# SEX.net
KiCad netlist of a schematic drawn in Altium Designer
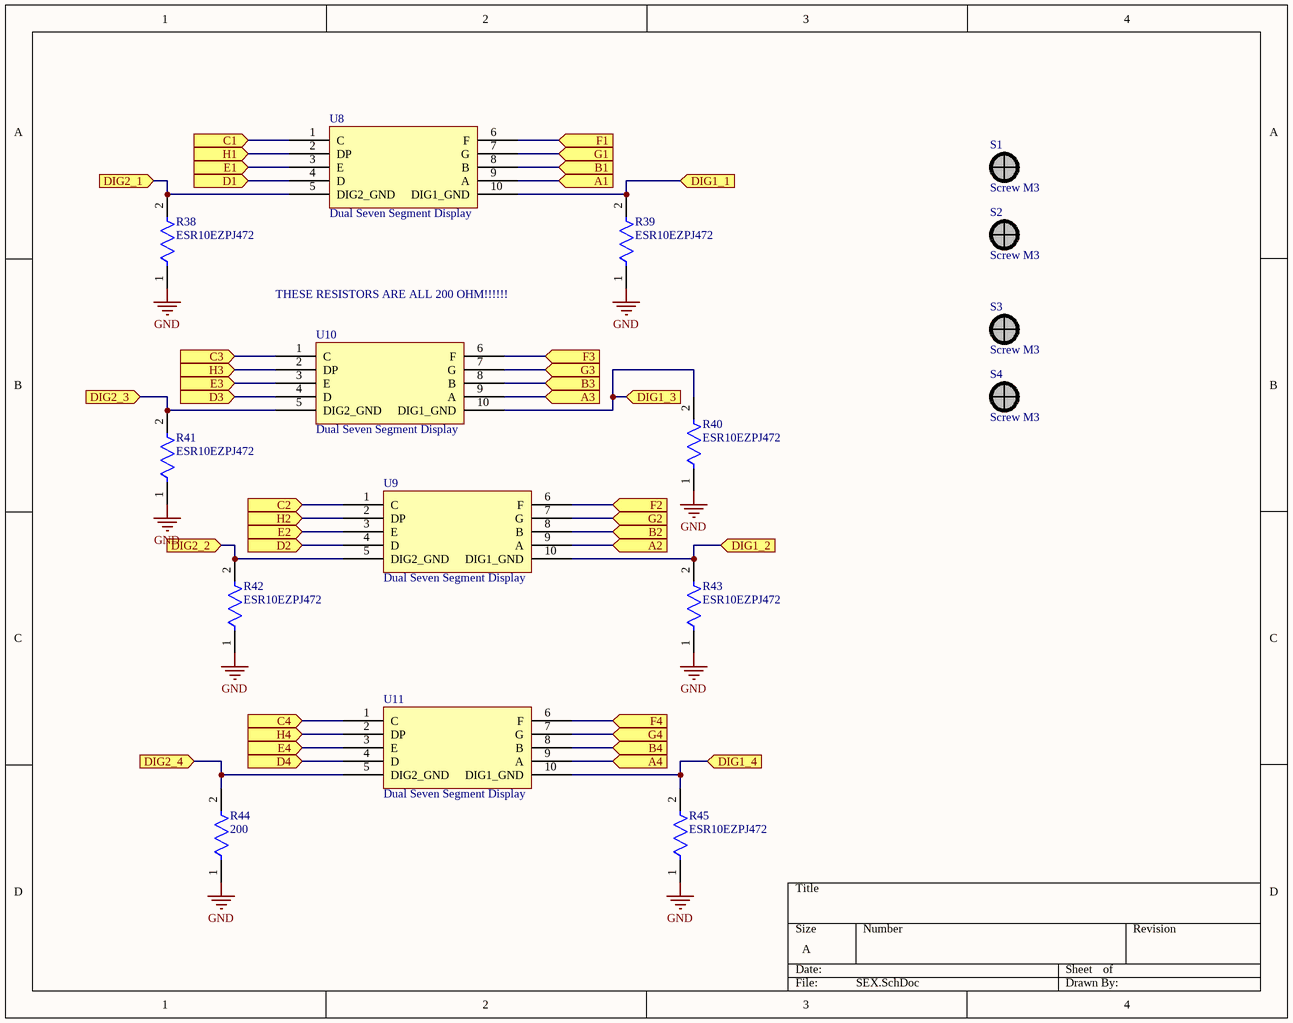
[diagram p0: SEX.SchDoc]

(export (version "E")
  (design (tool "Eeschema 10.0.6"))
  (components
    (comp (ref "R38")
      (value "ESR10EZPJ472")
      (footprint "FP-ESR10-IPC_B")
      (description "4.7kΩ ±5% 0.4W 0805 Anti-Surge Chip Resistor AEC-Q200")
      (fields (field (name "TOLERANCE") "5%"))
      (libsource (lib "Altium Content Vault") (part "1029c3af85768c4190bb7ad29bc67b5"))
    )
    (comp (ref "R39")
      (value "ESR10EZPJ472")
      (footprint "FP-ESR10-IPC_B")
      (description "4.7kΩ ±5% 0.4W 0805 Anti-Surge Chip Resistor AEC-Q200")
      (fields (field (name "TOLERANCE") "5%"))
      (libsource (lib "Altium Content Vault") (part "1029c3af85768c4190bb7ad29bc67b5"))
    )
    (comp (ref "R40")
      (value "ESR10EZPJ472")
      (footprint "FP-ESR10-IPC_B")
      (description "4.7kΩ ±5% 0.4W 0805 Anti-Surge Chip Resistor AEC-Q200")
      (fields (field (name "TOLERANCE") "5%"))
      (libsource (lib "Altium Content Vault") (part "1029c3af85768c4190bb7ad29bc67b5"))
    )
    (comp (ref "R41")
      (value "ESR10EZPJ472")
      (footprint "FP-ESR10-IPC_B")
      (description "4.7kΩ ±5% 0.4W 0805 Anti-Surge Chip Resistor AEC-Q200")
      (fields (field (name "TOLERANCE") "5%"))
      (libsource (lib "Altium Content Vault") (part "1029c3af85768c4190bb7ad29bc67b5"))
    )
    (comp (ref "R42")
      (value "ESR10EZPJ472")
      (footprint "FP-ESR10-IPC_B")
      (description "4.7kΩ ±5% 0.4W 0805 Anti-Surge Chip Resistor AEC-Q200")
      (fields (field (name "TOLERANCE") "5%"))
      (libsource (lib "Altium Content Vault") (part "1029c3af85768c4190bb7ad29bc67b5"))
    )
    (comp (ref "R43")
      (value "ESR10EZPJ472")
      (footprint "FP-ESR10-IPC_B")
      (description "4.7kΩ ±5% 0.4W 0805 Anti-Surge Chip Resistor AEC-Q200")
      (fields (field (name "TOLERANCE") "5%"))
      (libsource (lib "Altium Content Vault") (part "1029c3af85768c4190bb7ad29bc67b5"))
    )
    (comp (ref "R44")
      (value "200")
      (footprint "FP-ESR10-IPC_B")
      (description "4.7kΩ ±5% 0.4W 0805 Anti-Surge Chip Resistor AEC-Q200")
      (fields (field (name "TOLERANCE") "5%"))
      (libsource (lib "Altium Content Vault") (part "1029c3af85768c4190bb7ad29bc67b5"))
    )
    (comp (ref "R45")
      (value "ESR10EZPJ472")
      (footprint "FP-ESR10-IPC_B")
      (description "4.7kΩ ±5% 0.4W 0805 Anti-Surge Chip Resistor AEC-Q200")
      (fields (field (name "TOLERANCE") "5%"))
      (libsource (lib "Altium Content Vault") (part "1029c3af85768c4190bb7ad29bc67b5"))
    )
    (comp (ref "S1")
      (value "Screw M3")
      (footprint "Screw M3")
      (libsource (lib "Mechanical") (part "Screw M3"))
    )
    (comp (ref "S2")
      (value "Screw M3")
      (footprint "Screw M3")
      (libsource (lib "Mechanical") (part "Screw M3"))
    )
    (comp (ref "S3")
      (value "Screw M3")
      (footprint "Screw M3")
      (libsource (lib "Mechanical") (part "Screw M3"))
    )
    (comp (ref "S4")
      (value "Screw M3")
      (footprint "Screw M3")
      (libsource (lib "Mechanical") (part "Screw M3"))
    )
    (comp (ref "U8")
      (value "Dual Seven Segment Display")
      (footprint "DIP10")
      (libsource (lib "dualsseg") (part "Component_1"))
    )
    (comp (ref "U9")
      (value "Dual Seven Segment Display")
      (footprint "DIP10")
      (libsource (lib "dualsseg") (part "Component_1"))
    )
    (comp (ref "U10")
      (value "Dual Seven Segment Display")
      (footprint "DIP10")
      (libsource (lib "dualsseg") (part "Component_1"))
    )
    (comp (ref "U11")
      (value "Dual Seven Segment Display")
      (footprint "DIP10")
      (libsource (lib "dualsseg") (part "Component_1"))
    )
  )
  (nets
    (net (code "1") (name "/A1") (class "Default")
      (node (ref "U8") (pin "9") (pinfunction "A_9") (pintype "passive"))
    )
    (net (code "2") (name "/A2") (class "Default")
      (node (ref "U9") (pin "9") (pinfunction "A_9") (pintype "passive"))
    )
    (net (code "3") (name "/A3") (class "Default")
      (node (ref "U10") (pin "9") (pinfunction "A_9") (pintype "passive"))
    )
    (net (code "4") (name "/A4") (class "Default")
      (node (ref "U11") (pin "9") (pinfunction "A_9") (pintype "passive"))
    )
    (net (code "5") (name "/B1") (class "Default")
      (node (ref "U8") (pin "8") (pinfunction "B_8") (pintype "passive"))
    )
    (net (code "6") (name "/B2") (class "Default")
      (node (ref "U9") (pin "8") (pinfunction "B_8") (pintype "passive"))
    )
    (net (code "7") (name "/B3") (class "Default")
      (node (ref "U10") (pin "8") (pinfunction "B_8") (pintype "passive"))
    )
    (net (code "8") (name "/B4") (class "Default")
      (node (ref "U11") (pin "8") (pinfunction "B_8") (pintype "passive"))
    )
    (net (code "9") (name "/C1") (class "Default")
      (node (ref "U8") (pin "1") (pinfunction "C_1") (pintype "passive"))
    )
    (net (code "10") (name "/C2") (class "Default")
      (node (ref "U9") (pin "1") (pinfunction "C_1") (pintype "passive"))
    )
    (net (code "11") (name "/C3") (class "Default")
      (node (ref "U10") (pin "1") (pinfunction "C_1") (pintype "passive"))
    )
    (net (code "12") (name "/C4") (class "Default")
      (node (ref "U11") (pin "1") (pinfunction "C_1") (pintype "passive"))
    )
    (net (code "13") (name "/D1") (class "Default")
      (node (ref "U8") (pin "4") (pinfunction "D_4") (pintype "passive"))
    )
    (net (code "14") (name "/D2") (class "Default")
      (node (ref "U9") (pin "4") (pinfunction "D_4") (pintype "passive"))
    )
    (net (code "15") (name "/D3") (class "Default")
      (node (ref "U10") (pin "4") (pinfunction "D_4") (pintype "passive"))
    )
    (net (code "16") (name "/D4") (class "Default")
      (node (ref "U11") (pin "4") (pinfunction "D_4") (pintype "passive"))
    )
    (net (code "17") (name "/DIG1_1") (class "Default")
      (node (ref "R39") (pin "2") (pinfunction "2_2") (pintype "passive"))
      (node (ref "U8") (pin "10") (pinfunction "DIG1_GND_10") (pintype "passive"))
    )
    (net (code "18") (name "/DIG1_2") (class "Default")
      (node (ref "R43") (pin "2") (pinfunction "2_2") (pintype "passive"))
      (node (ref "U9") (pin "10") (pinfunction "DIG1_GND_10") (pintype "passive"))
    )
    (net (code "19") (name "/DIG1_3") (class "Default")
      (node (ref "R40") (pin "2") (pinfunction "2_2") (pintype "passive"))
      (node (ref "U10") (pin "10") (pinfunction "DIG1_GND_10") (pintype "passive"))
    )
    (net (code "20") (name "/DIG1_4") (class "Default")
      (node (ref "R45") (pin "2") (pinfunction "2_2") (pintype "passive"))
      (node (ref "U11") (pin "10") (pinfunction "DIG1_GND_10") (pintype "passive"))
    )
    (net (code "21") (name "/DIG2_1") (class "Default")
      (node (ref "R38") (pin "2") (pinfunction "2_2") (pintype "passive"))
      (node (ref "U8") (pin "5") (pinfunction "DIG2_GND_5") (pintype "passive"))
    )
    (net (code "22") (name "/DIG2_2") (class "Default")
      (node (ref "R42") (pin "2") (pinfunction "2_2") (pintype "passive"))
      (node (ref "U9") (pin "5") (pinfunction "DIG2_GND_5") (pintype "passive"))
    )
    (net (code "23") (name "/DIG2_3") (class "Default")
      (node (ref "R41") (pin "2") (pinfunction "2_2") (pintype "passive"))
      (node (ref "U10") (pin "5") (pinfunction "DIG2_GND_5") (pintype "passive"))
    )
    (net (code "24") (name "/DIG2_4") (class "Default")
      (node (ref "R44") (pin "2") (pinfunction "2_2") (pintype "passive"))
      (node (ref "U11") (pin "5") (pinfunction "DIG2_GND_5") (pintype "passive"))
    )
    (net (code "25") (name "/E1") (class "Default")
      (node (ref "U8") (pin "3") (pinfunction "E_3") (pintype "passive"))
    )
    (net (code "26") (name "/E2") (class "Default")
      (node (ref "U9") (pin "3") (pinfunction "E_3") (pintype "passive"))
    )
    (net (code "27") (name "/E3") (class "Default")
      (node (ref "U10") (pin "3") (pinfunction "E_3") (pintype "passive"))
    )
    (net (code "28") (name "/E4") (class "Default")
      (node (ref "U11") (pin "3") (pinfunction "E_3") (pintype "passive"))
    )
    (net (code "29") (name "/F1") (class "Default")
      (node (ref "U8") (pin "6") (pinfunction "F_6") (pintype "passive"))
    )
    (net (code "30") (name "/F2") (class "Default")
      (node (ref "U9") (pin "6") (pinfunction "F_6") (pintype "passive"))
    )
    (net (code "31") (name "/F3") (class "Default")
      (node (ref "U10") (pin "6") (pinfunction "F_6") (pintype "passive"))
    )
    (net (code "32") (name "/F4") (class "Default")
      (node (ref "U11") (pin "6") (pinfunction "F_6") (pintype "passive"))
    )
    (net (code "33") (name "/G1") (class "Default")
      (node (ref "U8") (pin "7") (pinfunction "G_7") (pintype "passive"))
    )
    (net (code "34") (name "/G2") (class "Default")
      (node (ref "U9") (pin "7") (pinfunction "G_7") (pintype "passive"))
    )
    (net (code "35") (name "/G3") (class "Default")
      (node (ref "U10") (pin "7") (pinfunction "G_7") (pintype "passive"))
    )
    (net (code "36") (name "/G4") (class "Default")
      (node (ref "U11") (pin "7") (pinfunction "G_7") (pintype "passive"))
    )
    (net (code "37") (name "/H1") (class "Default")
      (node (ref "U8") (pin "2") (pinfunction "DP_2") (pintype "passive"))
    )
    (net (code "38") (name "/H2") (class "Default")
      (node (ref "U9") (pin "2") (pinfunction "DP_2") (pintype "passive"))
    )
    (net (code "39") (name "/H3") (class "Default")
      (node (ref "U10") (pin "2") (pinfunction "DP_2") (pintype "passive"))
    )
    (net (code "40") (name "/H4") (class "Default")
      (node (ref "U11") (pin "2") (pinfunction "DP_2") (pintype "passive"))
    )
    (net (code "41") (name "GND") (class "Default")
      (node (ref "R38") (pin "1") (pinfunction "1_1") (pintype "passive"))
      (node (ref "R39") (pin "1") (pinfunction "1_1") (pintype "passive"))
      (node (ref "R40") (pin "1") (pinfunction "1_1") (pintype "passive"))
      (node (ref "R41") (pin "1") (pinfunction "1_1") (pintype "passive"))
      (node (ref "R42") (pin "1") (pinfunction "1_1") (pintype "passive"))
      (node (ref "R43") (pin "1") (pinfunction "1_1") (pintype "passive"))
      (node (ref "R44") (pin "1") (pinfunction "1_1") (pintype "passive"))
      (node (ref "R45") (pin "1") (pinfunction "1_1") (pintype "passive"))
    )
  )
)
